# Connectors.net
KiCad netlist of a schematic drawn in Altium Designer
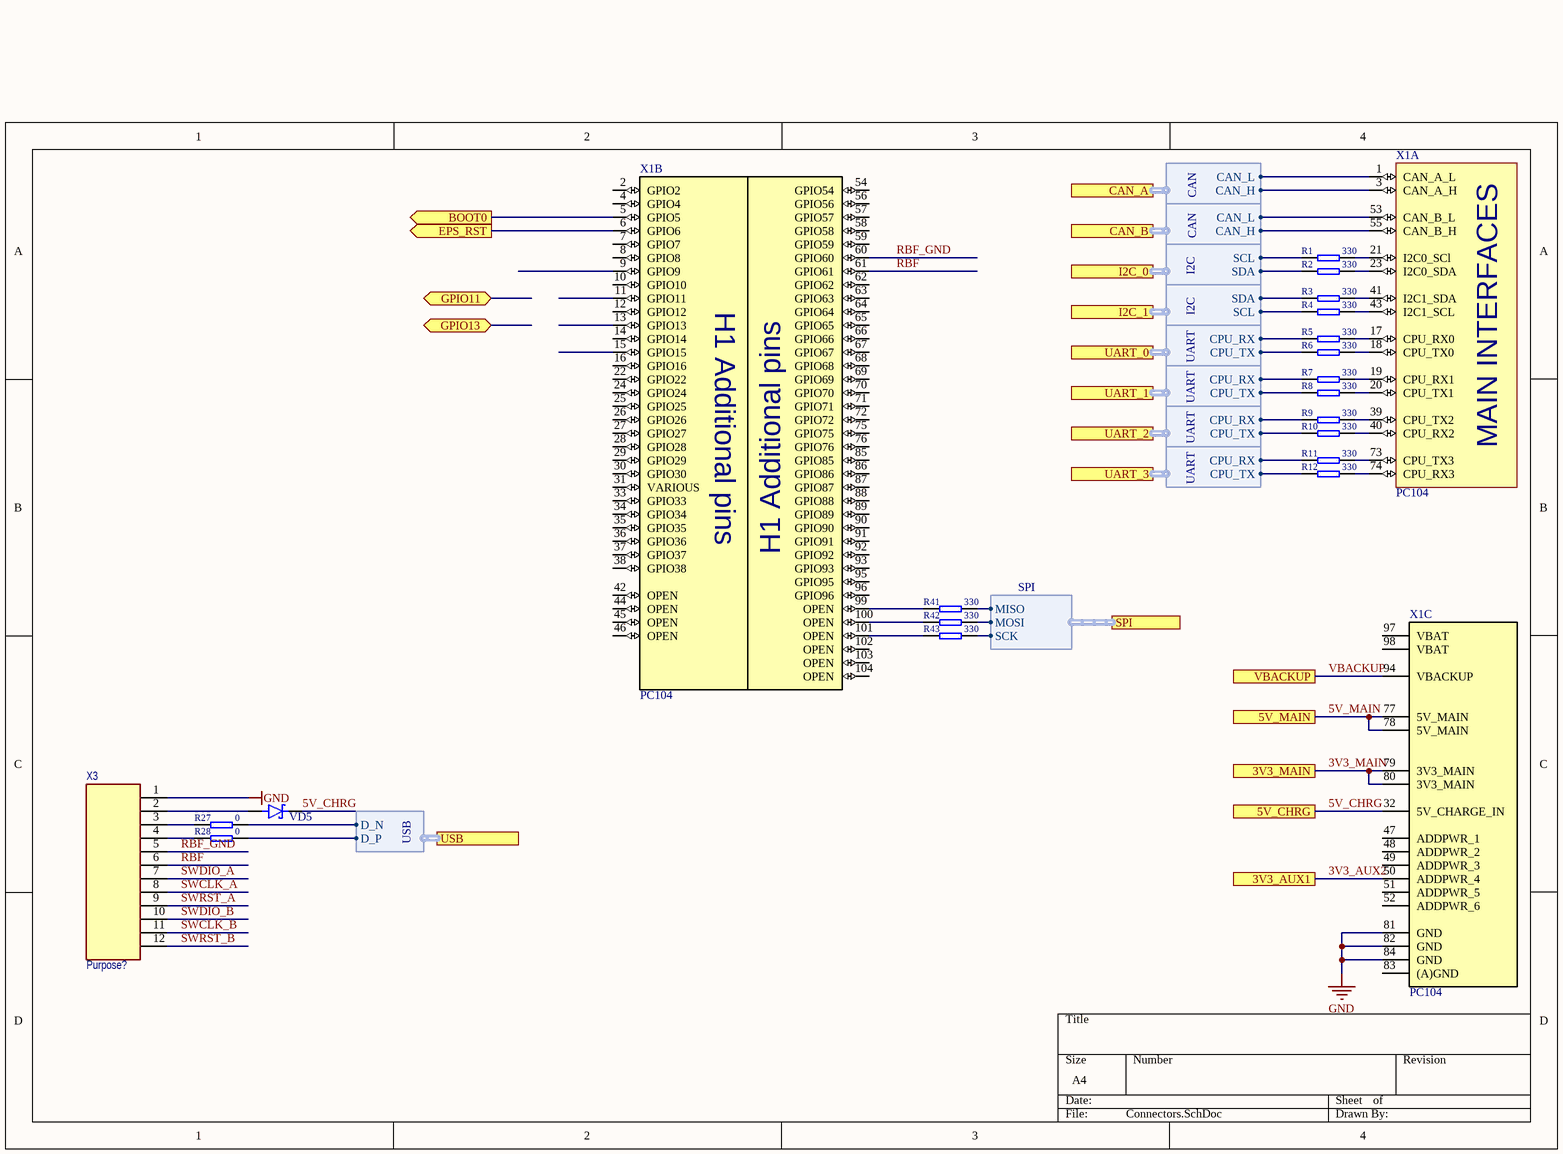
[diagram p0: Connectors.SchDoc]

(export (version "E")
  (design (tool "Eeschema 10.0.6"))
  (components
    (comp (ref "R1")
      (value "330")
      (footprint "RES 0603")
      (description "Resistor")
      (fields (field (name "Comment") "RES 0603 330"))
      (libsource (lib "!main") (part "!Resistor"))
    )
    (comp (ref "R2")
      (value "330")
      (footprint "RES 0603")
      (description "Resistor")
      (fields (field (name "Comment") "RES 0603 330"))
      (libsource (lib "!main") (part "!Resistor"))
    )
    (comp (ref "R3")
      (value "330")
      (footprint "RES 0603")
      (description "Resistor")
      (fields (field (name "Comment") "RES 0603 330"))
      (libsource (lib "!main") (part "!Resistor"))
    )
    (comp (ref "R4")
      (value "330")
      (footprint "RES 0603")
      (description "Resistor")
      (fields (field (name "Comment") "RES 0603 330"))
      (libsource (lib "!main") (part "!Resistor"))
    )
    (comp (ref "R5")
      (value "330")
      (footprint "RES 0603")
      (description "Resistor")
      (fields (field (name "Comment") "RES 0603 330"))
      (libsource (lib "!main") (part "!Resistor"))
    )
    (comp (ref "R6")
      (value "330")
      (footprint "RES 0603")
      (description "Resistor")
      (fields (field (name "Comment") "RES 0603 330"))
      (libsource (lib "!main") (part "!Resistor"))
    )
    (comp (ref "R7")
      (value "330")
      (footprint "RES 0603")
      (description "Resistor")
      (fields (field (name "Comment") "RES 0603 330"))
      (libsource (lib "!main") (part "!Resistor"))
    )
    (comp (ref "R8")
      (value "330")
      (footprint "RES 0603")
      (description "Resistor")
      (fields (field (name "Comment") "RES 0603 330"))
      (libsource (lib "!main") (part "!Resistor"))
    )
    (comp (ref "R9")
      (value "330")
      (footprint "RES 0603")
      (description "Resistor")
      (fields (field (name "Comment") "RES 0603 330"))
      (libsource (lib "!main") (part "!Resistor"))
    )
    (comp (ref "R10")
      (value "330")
      (footprint "RES 0603")
      (description "Resistor")
      (fields (field (name "Comment") "RES 0603 330"))
      (libsource (lib "!main") (part "!Resistor"))
    )
    (comp (ref "R11")
      (value "330")
      (footprint "RES 0603")
      (description "Resistor")
      (fields (field (name "Comment") "RES 0603 330"))
      (libsource (lib "!main") (part "!Resistor"))
    )
    (comp (ref "R12")
      (value "330")
      (footprint "RES 0603")
      (description "Resistor")
      (fields (field (name "Comment") "RES 0603 330"))
      (libsource (lib "!main") (part "!Resistor"))
    )
    (comp (ref "R27")
      (value "0")
      (footprint "RES 0603")
      (description "Resistor")
      (fields (field (name "Comment") "RES 0603 0"))
      (libsource (lib "!main") (part "!Resistor"))
    )
    (comp (ref "R28")
      (value "0")
      (footprint "RES 0603")
      (description "Resistor")
      (fields (field (name "Comment") "RES 0603 0"))
      (libsource (lib "!main") (part "!Resistor"))
    )
    (comp (ref "R41")
      (value "330")
      (footprint "RES 0603")
      (description "Resistor")
      (fields (field (name "Comment") "RES 0603 330"))
      (libsource (lib "!main") (part "!Resistor"))
    )
    (comp (ref "R42")
      (value "330")
      (footprint "RES 0603")
      (description "Resistor")
      (fields (field (name "Comment") "RES 0603 330"))
      (libsource (lib "!main") (part "!Resistor"))
    )
    (comp (ref "R43")
      (value "330")
      (footprint "RES 0603")
      (description "Resistor")
      (fields (field (name "Comment") "RES 0603 330"))
      (libsource (lib "!main") (part "!Resistor"))
    )
    (comp (ref "VD5")
      (value "Shottly diode SOD-123")
      (footprint "SOD-123")
      (description "Diode Shottky")
      (libsource (lib "diodes") (part "DiodeS"))
    )
    (comp (ref "X1")
      (value "PC104")
      (footprint "PC104_ArianSpace")
      (description "PC104 connector")
      (libsource (lib "SergeyIvlev_tmp") (part "PC104_ArianSpace"))
    )
    (comp (ref "X3")
      (value "Header?")
      (footprint "PicoBlade_12P")
      (description "10x1 Header")
      (fields (field (name "PURPOSE") "Purpose?"))
      (libsource (lib "connectors") (part "Header 1x12"))
    )
  )
  (nets
    (net (code "8") (name "/3V3_AUX2") (class "Default")
      (node (ref "X1") (pin "50") (pinfunction "ADDPWR_4_50") (pintype "power_in"))
    )
    (net (code "9") (name "/3V3_MAIN") (class "Default")
      (node (ref "X1") (pin "79") (pinfunction "3V3_MAIN_79") (pintype "power_in"))
      (node (ref "X1") (pin "80") (pinfunction "3V3_MAIN_80") (pintype "power_in"))
    )
    (net (code "10") (name "/5V_CHRG") (class "Default")
      (node (ref "VD5") (pin "C") (pinfunction "Cathode_C") (pintype "passive"))
      (node (ref "X1") (pin "32") (pinfunction "5V_CHARGE_IN_32") (pintype "power_in"))
    )
    (net (code "11") (name "/5V_MAIN") (class "Default")
      (node (ref "X1") (pin "77") (pinfunction "5V_MAIN_77") (pintype "power_in"))
      (node (ref "X1") (pin "78") (pinfunction "5V_MAIN_78") (pintype "power_in"))
    )
    (net (code "12") (name "/BOOT0") (class "Default")
      (node (ref "X1") (pin "5") (pinfunction "GPIO5_5") (pintype "bidirectional"))
    )
    (net (code "14") (name "/D_N") (class "Default")
      (node (ref "R27") (pin "2") (pinfunction "12_2") (pintype "passive"))
    )
    (net (code "15") (name "/D_P") (class "Default")
      (node (ref "R28") (pin "2") (pinfunction "12_2") (pintype "passive"))
    )
    (net (code "16") (name "/EPS_RST") (class "Default")
      (node (ref "X1") (pin "6") (pinfunction "GPIO6_6") (pintype "bidirectional"))
    )
    (net (code "20") (name "/MISO") (class "Default")
      (node (ref "R41") (pin "2") (pinfunction "12_2") (pintype "passive"))
    )
    (net (code "21") (name "/MOSI") (class "Default")
      (node (ref "R42") (pin "2") (pinfunction "12_2") (pintype "passive"))
    )
    (net (code "22") (name "/RBF") (class "Default")
      (node (ref "X1") (pin "61") (pinfunction "GPIO61_61") (pintype "bidirectional"))
      (node (ref "X3") (pin "6") (pintype "passive"))
    )
    (net (code "23") (name "/RBF_GND") (class "Default")
      (node (ref "X1") (pin "60") (pinfunction "GPIO60_60") (pintype "bidirectional"))
      (node (ref "X3") (pin "5") (pintype "passive"))
    )
    (net (code "24") (name "/SCK") (class "Default")
      (node (ref "R43") (pin "2") (pinfunction "12_2") (pintype "passive"))
    )
    (net (code "25") (name "/SWCLK_A") (class "Default") (node (ref "X3") (pin "8") (pintype "passive")))
    (net (code "26") (name "/SWCLK_B") (class "Default") (node (ref "X3") (pin "11") (pintype "passive")))
    (net (code "27") (name "/SWDIO_A") (class "Default") (node (ref "X3") (pin "7") (pintype "passive")))
    (net (code "28") (name "/SWDIO_B") (class "Default") (node (ref "X3") (pin "10") (pintype "passive")))
    (net (code "29") (name "/SWRST_A") (class "Default") (node (ref "X3") (pin "9") (pintype "passive")))
    (net (code "30") (name "/SWRST_B") (class "Default") (node (ref "X3") (pin "12") (pintype "passive")))
    (net (code "31") (name "/VBACKUP") (class "Default")
      (node (ref "X1") (pin "94") (pinfunction "VBACKUP_94") (pintype "power_in"))
    )
    (net (code "37") (name "GND") (class "Default")
      (node (ref "X1") (pin "81") (pinfunction "GND_81") (pintype "power_in"))
      (node (ref "X1") (pin "82") (pinfunction "GND_82") (pintype "power_in"))
      (node (ref "X1") (pin "84") (pinfunction "GND_84") (pintype "power_in"))
      (node (ref "X3") (pin "1") (pintype "passive"))
    )
    (net (code "38") (name "Net-(R1-12)") (class "Default")
      (node (ref "R1") (pin "2") (pinfunction "12_2") (pintype "passive"))
      (node (ref "X1") (pin "21") (pinfunction "I2C0_SCl_21") (pintype "bidirectional"))
    )
    (net (code "39") (name "Net-(R2-12)") (class "Default")
      (node (ref "R2") (pin "2") (pinfunction "12_2") (pintype "passive"))
      (node (ref "X1") (pin "23") (pinfunction "I2C0_SDA_23") (pintype "bidirectional"))
    )
    (net (code "40") (name "Net-(R3-12)") (class "Default")
      (node (ref "R3") (pin "2") (pinfunction "12_2") (pintype "passive"))
      (node (ref "X1") (pin "41") (pinfunction "I2C1_SDA_41") (pintype "bidirectional"))
    )
    (net (code "41") (name "Net-(R4-12)") (class "Default")
      (node (ref "R4") (pin "2") (pinfunction "12_2") (pintype "passive"))
      (node (ref "X1") (pin "43") (pinfunction "I2C1_SCL_43") (pintype "bidirectional"))
    )
    (net (code "42") (name "Net-(R5-12)") (class "Default")
      (node (ref "R5") (pin "2") (pinfunction "12_2") (pintype "passive"))
      (node (ref "X1") (pin "17") (pinfunction "CPU_RX0_17") (pintype "bidirectional"))
    )
    (net (code "43") (name "Net-(R6-12)") (class "Default")
      (node (ref "R6") (pin "2") (pinfunction "12_2") (pintype "passive"))
      (node (ref "X1") (pin "18") (pinfunction "CPU_TX0_18") (pintype "bidirectional"))
    )
    (net (code "44") (name "Net-(R7-12)") (class "Default")
      (node (ref "R7") (pin "2") (pinfunction "12_2") (pintype "passive"))
      (node (ref "X1") (pin "19") (pinfunction "CPU_RX1_19") (pintype "bidirectional"))
    )
    (net (code "45") (name "Net-(R8-12)") (class "Default")
      (node (ref "R8") (pin "2") (pinfunction "12_2") (pintype "passive"))
      (node (ref "X1") (pin "20") (pinfunction "CPU_TX1_20") (pintype "bidirectional"))
    )
    (net (code "46") (name "Net-(R9-12)") (class "Default")
      (node (ref "R9") (pin "2") (pinfunction "12_2") (pintype "passive"))
      (node (ref "X1") (pin "39") (pinfunction "CPU_TX2_39") (pintype "bidirectional"))
    )
    (net (code "47") (name "Net-(R10-12)") (class "Default")
      (node (ref "R10") (pin "2") (pinfunction "12_2") (pintype "passive"))
      (node (ref "X1") (pin "40") (pinfunction "CPU_RX2_40") (pintype "bidirectional"))
    )
    (net (code "48") (name "Net-(R11-12)") (class "Default")
      (node (ref "R11") (pin "2") (pinfunction "12_2") (pintype "passive"))
      (node (ref "X1") (pin "73") (pinfunction "CPU_TX3_73") (pintype "bidirectional"))
    )
    (net (code "49") (name "Net-(R12-12)") (class "Default")
      (node (ref "R12") (pin "2") (pinfunction "12_2") (pintype "passive"))
      (node (ref "X1") (pin "74") (pinfunction "CPU_RX3_74") (pintype "bidirectional"))
    )
    (net (code "50") (name "Net-(R27-11)") (class "Default")
      (node (ref "R27") (pin "1") (pinfunction "11_1") (pintype "passive"))
      (node (ref "X3") (pin "3") (pintype "passive"))
    )
    (net (code "51") (name "Net-(R28-11)") (class "Default")
      (node (ref "R28") (pin "1") (pinfunction "11_1") (pintype "passive"))
      (node (ref "X3") (pin "4") (pintype "passive"))
    )
    (net (code "52") (name "Net-(R41-11)") (class "Default")
      (node (ref "R41") (pin "1") (pinfunction "11_1") (pintype "passive"))
      (node (ref "X1") (pin "99") (pinfunction "OPEN_99") (pintype "bidirectional"))
    )
    (net (code "53") (name "Net-(R42-11)") (class "Default")
      (node (ref "R42") (pin "1") (pinfunction "11_1") (pintype "passive"))
      (node (ref "X1") (pin "100") (pinfunction "OPEN_100") (pintype "bidirectional"))
    )
    (net (code "54") (name "Net-(R43-11)") (class "Default")
      (node (ref "R43") (pin "1") (pinfunction "11_1") (pintype "passive"))
      (node (ref "X1") (pin "101") (pinfunction "OPEN_101") (pintype "bidirectional"))
    )
    (net (code "55") (name "Net-(VD5-Anode)") (class "Default")
      (node (ref "VD5") (pin "A") (pinfunction "Anode_A") (pintype "passive"))
      (node (ref "X3") (pin "2") (pintype "passive"))
    )
    (net (code "56") (name "unconnected-(R1-11-Pad1)") (class "Default")
      (node (ref "R1") (pin "1") (pinfunction "11_1") (pintype "passive"))
    )
    (net (code "57") (name "unconnected-(R2-11-Pad1)") (class "Default")
      (node (ref "R2") (pin "1") (pinfunction "11_1") (pintype "passive"))
    )
    (net (code "58") (name "unconnected-(R3-11-Pad1)") (class "Default")
      (node (ref "R3") (pin "1") (pinfunction "11_1") (pintype "passive"))
    )
    (net (code "59") (name "unconnected-(R4-11-Pad1)") (class "Default")
      (node (ref "R4") (pin "1") (pinfunction "11_1") (pintype "passive"))
    )
    (net (code "60") (name "unconnected-(R5-11-Pad1)") (class "Default")
      (node (ref "R5") (pin "1") (pinfunction "11_1") (pintype "passive"))
    )
    (net (code "61") (name "unconnected-(R6-11-Pad1)") (class "Default")
      (node (ref "R6") (pin "1") (pinfunction "11_1") (pintype "passive"))
    )
    (net (code "62") (name "unconnected-(R7-11-Pad1)") (class "Default")
      (node (ref "R7") (pin "1") (pinfunction "11_1") (pintype "passive"))
    )
    (net (code "63") (name "unconnected-(R8-11-Pad1)") (class "Default")
      (node (ref "R8") (pin "1") (pinfunction "11_1") (pintype "passive"))
    )
    (net (code "64") (name "unconnected-(R9-11-Pad1)") (class "Default")
      (node (ref "R9") (pin "1") (pinfunction "11_1") (pintype "passive"))
    )
    (net (code "65") (name "unconnected-(R10-11-Pad1)") (class "Default")
      (node (ref "R10") (pin "1") (pinfunction "11_1") (pintype "passive"))
    )
    (net (code "66") (name "unconnected-(R11-11-Pad1)") (class "Default")
      (node (ref "R11") (pin "1") (pinfunction "11_1") (pintype "passive"))
    )
    (net (code "67") (name "unconnected-(R12-11-Pad1)") (class "Default")
      (node (ref "R12") (pin "1") (pinfunction "11_1") (pintype "passive"))
    )
    (net (code "68") (name "unconnected-(X1A-CAN_A_H-Pad3)") (class "Default")
      (node (ref "X1") (pin "3") (pinfunction "CAN_A_H_3") (pintype "bidirectional"))
    )
    (net (code "69") (name "unconnected-(X1A-CAN_A_L-Pad1)") (class "Default")
      (node (ref "X1") (pin "1") (pinfunction "CAN_A_L_1") (pintype "bidirectional"))
    )
    (net (code "70") (name "unconnected-(X1A-CAN_B_H-Pad55)") (class "Default")
      (node (ref "X1") (pin "55") (pinfunction "CAN_B_H_55") (pintype "bidirectional"))
    )
    (net (code "71") (name "unconnected-(X1A-CAN_B_L-Pad53)") (class "Default")
      (node (ref "X1") (pin "53") (pinfunction "CAN_B_L_53") (pintype "bidirectional"))
    )
    (net (code "72") (name "unconnected-(X1B-GPIO2-Pad2)") (class "Default")
      (node (ref "X1") (pin "2") (pinfunction "GPIO2_2") (pintype "bidirectional"))
    )
    (net (code "73") (name "unconnected-(X1B-GPIO4-Pad4)") (class "Default")
      (node (ref "X1") (pin "4") (pinfunction "GPIO4_4") (pintype "bidirectional"))
    )
    (net (code "74") (name "unconnected-(X1B-GPIO7-Pad7)") (class "Default")
      (node (ref "X1") (pin "7") (pinfunction "GPIO7_7") (pintype "bidirectional"))
    )
    (net (code "75") (name "unconnected-(X1B-GPIO8-Pad8)") (class "Default")
      (node (ref "X1") (pin "8") (pinfunction "GPIO8_8") (pintype "bidirectional"))
    )
    (net (code "76") (name "unconnected-(X1B-GPIO9-Pad9)") (class "Default")
      (node (ref "X1") (pin "9") (pinfunction "GPIO9_9") (pintype "bidirectional"))
    )
    (net (code "77") (name "unconnected-(X1B-GPIO10-Pad10)") (class "Default")
      (node (ref "X1") (pin "10") (pinfunction "GPIO10_10") (pintype "bidirectional"))
    )
    (net (code "78") (name "unconnected-(X1B-GPIO11-Pad11)") (class "Default")
      (node (ref "X1") (pin "11") (pinfunction "GPIO11_11") (pintype "bidirectional"))
    )
    (net (code "79") (name "unconnected-(X1B-GPIO12-Pad12)") (class "Default")
      (node (ref "X1") (pin "12") (pinfunction "GPIO12_12") (pintype "bidirectional"))
    )
    (net (code "80") (name "unconnected-(X1B-GPIO13-Pad13)") (class "Default")
      (node (ref "X1") (pin "13") (pinfunction "GPIO13_13") (pintype "bidirectional"))
    )
    (net (code "81") (name "unconnected-(X1B-GPIO14-Pad14)") (class "Default")
      (node (ref "X1") (pin "14") (pinfunction "GPIO14_14") (pintype "bidirectional"))
    )
    (net (code "82") (name "unconnected-(X1B-GPIO15-Pad15)") (class "Default")
      (node (ref "X1") (pin "15") (pinfunction "GPIO15_15") (pintype "bidirectional"))
    )
    (net (code "83") (name "unconnected-(X1B-GPIO16-Pad16)") (class "Default")
      (node (ref "X1") (pin "16") (pinfunction "GPIO16_16") (pintype "bidirectional"))
    )
    (net (code "84") (name "unconnected-(X1B-GPIO22-Pad22)") (class "Default")
      (node (ref "X1") (pin "22") (pinfunction "GPIO22_22") (pintype "bidirectional"))
    )
    (net (code "85") (name "unconnected-(X1B-GPIO24-Pad24)") (class "Default")
      (node (ref "X1") (pin "24") (pinfunction "GPIO24_24") (pintype "bidirectional"))
    )
    (net (code "86") (name "unconnected-(X1B-GPIO25-Pad25)") (class "Default")
      (node (ref "X1") (pin "25") (pinfunction "GPIO25_25") (pintype "bidirectional"))
    )
    (net (code "87") (name "unconnected-(X1B-GPIO26-Pad26)") (class "Default")
      (node (ref "X1") (pin "26") (pinfunction "GPIO26_26") (pintype "bidirectional"))
    )
    (net (code "88") (name "unconnected-(X1B-GPIO27-Pad27)") (class "Default")
      (node (ref "X1") (pin "27") (pinfunction "GPIO27_27") (pintype "bidirectional"))
    )
    (net (code "89") (name "unconnected-(X1B-GPIO28-Pad28)") (class "Default")
      (node (ref "X1") (pin "28") (pinfunction "GPIO28_28") (pintype "bidirectional"))
    )
    (net (code "90") (name "unconnected-(X1B-GPIO29-Pad29)") (class "Default")
      (node (ref "X1") (pin "29") (pinfunction "GPIO29_29") (pintype "bidirectional"))
    )
    (net (code "91") (name "unconnected-(X1B-GPIO30-Pad30)") (class "Default")
      (node (ref "X1") (pin "30") (pinfunction "GPIO30_30") (pintype "bidirectional"))
    )
    (net (code "92") (name "unconnected-(X1B-GPIO33-Pad33)") (class "Default")
      (node (ref "X1") (pin "33") (pinfunction "GPIO33_33") (pintype "bidirectional"))
    )
    (net (code "93") (name "unconnected-(X1B-GPIO34-Pad34)") (class "Default")
      (node (ref "X1") (pin "34") (pinfunction "GPIO34_34") (pintype "bidirectional"))
    )
    (net (code "94") (name "unconnected-(X1B-GPIO35-Pad35)") (class "Default")
      (node (ref "X1") (pin "35") (pinfunction "GPIO35_35") (pintype "bidirectional"))
    )
    (net (code "95") (name "unconnected-(X1B-GPIO36-Pad36)") (class "Default")
      (node (ref "X1") (pin "36") (pinfunction "GPIO36_36") (pintype "bidirectional"))
    )
    (net (code "96") (name "unconnected-(X1B-GPIO37-Pad37)") (class "Default")
      (node (ref "X1") (pin "37") (pinfunction "GPIO37_37") (pintype "bidirectional"))
    )
    (net (code "97") (name "unconnected-(X1B-GPIO38-Pad38)") (class "Default")
      (node (ref "X1") (pin "38") (pinfunction "GPIO38_38") (pintype "bidirectional"))
    )
    (net (code "98") (name "unconnected-(X1B-GPIO54-Pad54)") (class "Default")
      (node (ref "X1") (pin "54") (pinfunction "GPIO54_54") (pintype "bidirectional"))
    )
    (net (code "99") (name "unconnected-(X1B-GPIO56-Pad56)") (class "Default")
      (node (ref "X1") (pin "56") (pinfunction "GPIO56_56") (pintype "bidirectional"))
    )
    (net (code "100") (name "unconnected-(X1B-GPIO57-Pad57)") (class "Default")
      (node (ref "X1") (pin "57") (pinfunction "GPIO57_57") (pintype "bidirectional"))
    )
    (net (code "101") (name "unconnected-(X1B-GPIO58-Pad58)") (class "Default")
      (node (ref "X1") (pin "58") (pinfunction "GPIO58_58") (pintype "bidirectional"))
    )
    (net (code "102") (name "unconnected-(X1B-GPIO59-Pad59)") (class "Default")
      (node (ref "X1") (pin "59") (pinfunction "GPIO59_59") (pintype "bidirectional"))
    )
    (net (code "103") (name "unconnected-(X1B-GPIO62-Pad62)") (class "Default")
      (node (ref "X1") (pin "62") (pinfunction "GPIO62_62") (pintype "bidirectional"))
    )
    (net (code "104") (name "unconnected-(X1B-GPIO63-Pad63)") (class "Default")
      (node (ref "X1") (pin "63") (pinfunction "GPIO63_63") (pintype "bidirectional"))
    )
    (net (code "105") (name "unconnected-(X1B-GPIO64-Pad64)") (class "Default")
      (node (ref "X1") (pin "64") (pinfunction "GPIO64_64") (pintype "bidirectional"))
    )
    (net (code "106") (name "unconnected-(X1B-GPIO65-Pad65)") (class "Default")
      (node (ref "X1") (pin "65") (pinfunction "GPIO65_65") (pintype "bidirectional"))
    )
    (net (code "107") (name "unconnected-(X1B-GPIO66-Pad66)") (class "Default")
      (node (ref "X1") (pin "66") (pinfunction "GPIO66_66") (pintype "bidirectional"))
    )
    (net (code "108") (name "unconnected-(X1B-GPIO67-Pad67)") (class "Default")
      (node (ref "X1") (pin "67") (pinfunction "GPIO67_67") (pintype "bidirectional"))
    )
    (net (code "109") (name "unconnected-(X1B-GPIO68-Pad68)") (class "Default")
      (node (ref "X1") (pin "68") (pinfunction "GPIO68_68") (pintype "bidirectional"))
    )
    (net (code "110") (name "unconnected-(X1B-GPIO69-Pad69)") (class "Default")
      (node (ref "X1") (pin "69") (pinfunction "GPIO69_69") (pintype "bidirectional"))
    )
    (net (code "111") (name "unconnected-(X1B-GPIO70-Pad70)") (class "Default")
      (node (ref "X1") (pin "70") (pinfunction "GPIO70_70") (pintype "bidirectional"))
    )
    (net (code "112") (name "unconnected-(X1B-GPIO71-Pad71)") (class "Default")
      (node (ref "X1") (pin "71") (pinfunction "GPIO71_71") (pintype "bidirectional"))
    )
    (net (code "113") (name "unconnected-(X1B-GPIO72-Pad72)") (class "Default")
      (node (ref "X1") (pin "72") (pinfunction "GPIO72_72") (pintype "bidirectional"))
    )
    (net (code "114") (name "unconnected-(X1B-GPIO75-Pad75)") (class "Default")
      (node (ref "X1") (pin "75") (pinfunction "GPIO75_75") (pintype "bidirectional"))
    )
    (net (code "115") (name "unconnected-(X1B-GPIO76-Pad76)") (class "Default")
      (node (ref "X1") (pin "76") (pinfunction "GPIO76_76") (pintype "bidirectional"))
    )
    (net (code "116") (name "unconnected-(X1B-GPIO85-Pad85)") (class "Default")
      (node (ref "X1") (pin "85") (pinfunction "GPIO85_85") (pintype "bidirectional"))
    )
    (net (code "117") (name "unconnected-(X1B-GPIO86-Pad86)") (class "Default")
      (node (ref "X1") (pin "86") (pinfunction "GPIO86_86") (pintype "bidirectional"))
    )
    (net (code "118") (name "unconnected-(X1B-GPIO87-Pad87)") (class "Default")
      (node (ref "X1") (pin "87") (pinfunction "GPIO87_87") (pintype "bidirectional"))
    )
    (net (code "119") (name "unconnected-(X1B-GPIO88-Pad88)") (class "Default")
      (node (ref "X1") (pin "88") (pinfunction "GPIO88_88") (pintype "bidirectional"))
    )
    (net (code "120") (name "unconnected-(X1B-GPIO89-Pad89)") (class "Default")
      (node (ref "X1") (pin "89") (pinfunction "GPIO89_89") (pintype "bidirectional"))
    )
    (net (code "121") (name "unconnected-(X1B-GPIO90-Pad90)") (class "Default")
      (node (ref "X1") (pin "90") (pinfunction "GPIO90_90") (pintype "bidirectional"))
    )
    (net (code "122") (name "unconnected-(X1B-GPIO91-Pad91)") (class "Default")
      (node (ref "X1") (pin "91") (pinfunction "GPIO91_91") (pintype "bidirectional"))
    )
    (net (code "123") (name "unconnected-(X1B-GPIO92-Pad92)") (class "Default")
      (node (ref "X1") (pin "92") (pinfunction "GPIO92_92") (pintype "bidirectional"))
    )
    (net (code "124") (name "unconnected-(X1B-GPIO93-Pad93)") (class "Default")
      (node (ref "X1") (pin "93") (pinfunction "GPIO93_93") (pintype "bidirectional"))
    )
    (net (code "125") (name "unconnected-(X1B-GPIO95-Pad95)") (class "Default")
      (node (ref "X1") (pin "95") (pinfunction "GPIO95_95") (pintype "bidirectional"))
    )
    (net (code "126") (name "unconnected-(X1B-GPIO96-Pad96)") (class "Default")
      (node (ref "X1") (pin "96") (pinfunction "GPIO96_96") (pintype "bidirectional"))
    )
    (net (code "127") (name "unconnected-(X1B-OPEN-Pad42)") (class "Default")
      (node (ref "X1") (pin "42") (pinfunction "OPEN_42") (pintype "bidirectional"))
    )
    (net (code "128") (name "unconnected-(X1B-OPEN-Pad44)") (class "Default")
      (node (ref "X1") (pin "44") (pinfunction "OPEN_44") (pintype "bidirectional"))
    )
    (net (code "129") (name "unconnected-(X1B-OPEN-Pad45)") (class "Default")
      (node (ref "X1") (pin "45") (pinfunction "OPEN_45") (pintype "bidirectional"))
    )
    (net (code "130") (name "unconnected-(X1B-OPEN-Pad46)") (class "Default")
      (node (ref "X1") (pin "46") (pinfunction "OPEN_46") (pintype "bidirectional"))
    )
    (net (code "131") (name "unconnected-(X1B-OPEN-Pad102)") (class "Default")
      (node (ref "X1") (pin "102") (pinfunction "OPEN_102") (pintype "bidirectional"))
    )
    (net (code "132") (name "unconnected-(X1B-OPEN-Pad103)") (class "Default")
      (node (ref "X1") (pin "103") (pinfunction "OPEN_103") (pintype "bidirectional"))
    )
    (net (code "133") (name "unconnected-(X1B-OPEN-Pad104)") (class "Default")
      (node (ref "X1") (pin "104") (pinfunction "OPEN_104") (pintype "bidirectional"))
    )
    (net (code "134") (name "unconnected-(X1B-VARIOUS-Pad31)") (class "Default")
      (node (ref "X1") (pin "31") (pinfunction "VARIOUS_31") (pintype "bidirectional"))
    )
    (net (code "135") (name "unconnected-(X1C-(A)GND-Pad83)") (class "Default")
      (node (ref "X1") (pin "83") (pinfunction "(A)GND_83") (pintype "power_in"))
    )
    (net (code "136") (name "unconnected-(X1C-ADDPWR_1-Pad47)") (class "Default")
      (node (ref "X1") (pin "47") (pinfunction "ADDPWR_1_47") (pintype "power_in"))
    )
    (net (code "137") (name "unconnected-(X1C-ADDPWR_2-Pad48)") (class "Default")
      (node (ref "X1") (pin "48") (pinfunction "ADDPWR_2_48") (pintype "power_in"))
    )
    (net (code "138") (name "unconnected-(X1C-ADDPWR_3-Pad49)") (class "Default")
      (node (ref "X1") (pin "49") (pinfunction "ADDPWR_3_49") (pintype "power_in"))
    )
    (net (code "139") (name "unconnected-(X1C-ADDPWR_5-Pad51)") (class "Default")
      (node (ref "X1") (pin "51") (pinfunction "ADDPWR_5_51") (pintype "power_in"))
    )
    (net (code "140") (name "unconnected-(X1C-ADDPWR_6-Pad52)") (class "Default")
      (node (ref "X1") (pin "52") (pinfunction "ADDPWR_6_52") (pintype "power_in"))
    )
    (net (code "141") (name "unconnected-(X1C-VBAT-Pad97)") (class "Default")
      (node (ref "X1") (pin "97") (pinfunction "VBAT_97") (pintype "power_in"))
    )
    (net (code "142") (name "unconnected-(X1C-VBAT-Pad98)") (class "Default")
      (node (ref "X1") (pin "98") (pinfunction "VBAT_98") (pintype "power_in"))
    )
  )
)
